# LatchingFaultActiveHigh.net
KiCad netlist of a schematic drawn in Altium Designer
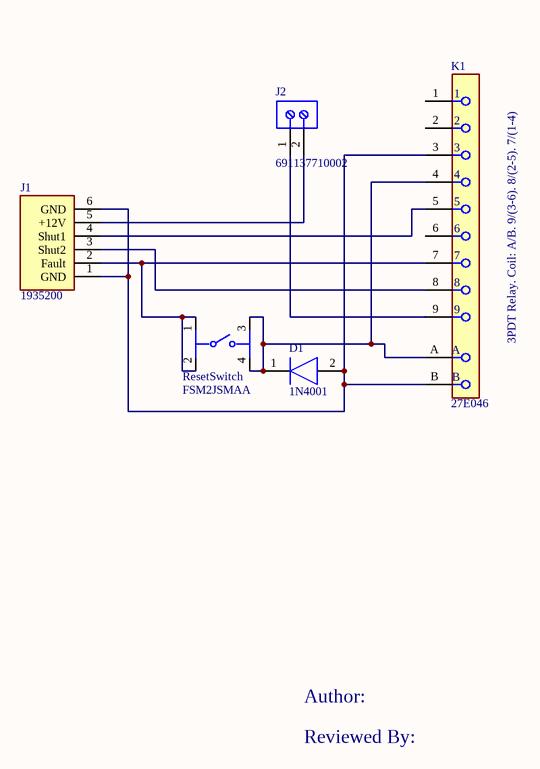
[diagram p0: LatchingFaultActiveHigh.SchDoc]

(export (version "E")
  (design (tool "Eeschema 10.0.6"))
  (components
    (comp (ref "D1")
      (value "1N4001")
      (footprint "SamacSys:DIOAD1410W86L470D235")
      (description "Diode")
      (libsource (lib "*") (part "1N4001"))
    )
    (comp (ref "J1")
      (value "1935200")
      (footprint "SamacSys:1935200")
      (description "Connector")
      (fields (field (name "MOUSER PART NUMBER") "651-1935200") (field (name "RS PART NUMBER") "8045509"))
      (libsource (lib "*") (part "1935200"))
    )
    (comp (ref "J2")
      (value "691137710002")
      (footprint "691137710002")
      (description "Series 1377 - 5.00 mm Horizontal Entry with Pressure Clamp WR-TBL, 2 pin")
      (fields (field (name "MANUFACTURER") "Wurth Elektronik") (field (name "PUBLISHER") "WurthElektronik"))
      (libsource (lib "Altium Content Vault") (part "WE-CN-1P-F-TB2"))
    )
    (comp (ref "K1")
      (value "27E046")
      (footprint "FP-27E046-MFG")
      (description "RELAY SOCKET 11 POS THROUGH HOLE")
      (fields
        (field (name "OCTOPART") "https://octopart.com/27e046-te+connectivity-39661310")
        (field (name "MANUFACTURER") "TE Connectivity")
      )
      (libsource (lib "Altium Content Vault") (part "d5e8f7d71913d095abaa3b4fe508f1c"))
    )
    (comp (ref "ResetSwitch")
      (value "FSM2JSMAA")
      (footprint "FP-FSM2JSMAA-MFG")
      (description "SWITCH TACTILE SPST-NO 0.05A 24V")
      (fields
        (field (name "MANUFACTURER") "TE Connectivity")
        (field (name "OCTOPART") "https://octopart.com/fsm2jsmaa-te+connectivity-41720620")
      )
      (libsource (lib "Altium Content Vault") (part "b8895f3f4cefb76e1819d2863dba89b"))
    )
  )
  (nets
    (net (code "1") (name "Net-(D1-A)") (class "Default")
      (node (ref "D1") (pin "2") (pinfunction "A_2") (pintype "passive"))
      (node (ref "J1") (pin "1") (pinfunction "GND_1") (pintype "passive"))
      (node (ref "J1") (pin "6") (pinfunction "GND_6") (pintype "passive"))
      (node (ref "K1") (pin "3") (pinfunction "3_3") (pintype "passive"))
      (node (ref "K1") (pin "B") (pinfunction "B_B") (pintype "passive"))
    )
    (net (code "2") (name "Net-(D1-K)") (class "Default")
      (node (ref "D1") (pin "1") (pinfunction "K_1") (pintype "passive"))
      (node (ref "K1") (pin "4") (pinfunction "4_4") (pintype "passive"))
      (node (ref "K1") (pin "A") (pinfunction "A_A") (pintype "passive"))
      (node (ref "ResetSwitch") (pin "3") (pinfunction "3_3") (pintype "passive"))
      (node (ref "ResetSwitch") (pin "4") (pinfunction "4_4") (pintype "passive"))
    )
    (net (code "3") (name "Net-(J1-+12V)") (class "Default")
      (node (ref "J1") (pin "5") (pinfunction "+12V_5") (pintype "passive"))
      (node (ref "J2") (pin "2") (pintype "passive"))
    )
    (net (code "4") (name "Net-(J1-Fault)") (class "Default")
      (node (ref "J1") (pin "2") (pinfunction "Fault_2") (pintype "passive"))
      (node (ref "K1") (pin "7") (pinfunction "7_7") (pintype "passive"))
      (node (ref "ResetSwitch") (pin "1") (pinfunction "1_1") (pintype "passive"))
      (node (ref "ResetSwitch") (pin "2") (pinfunction "2_2") (pintype "passive"))
    )
    (net (code "5") (name "Net-(J1-Shut1)") (class "Default")
      (node (ref "J1") (pin "4") (pinfunction "Shut1_4") (pintype "passive"))
      (node (ref "K1") (pin "5") (pinfunction "5_5") (pintype "passive"))
    )
    (net (code "6") (name "Net-(J1-Shut2)") (class "Default")
      (node (ref "J1") (pin "3") (pinfunction "Shut2_3") (pintype "passive"))
      (node (ref "K1") (pin "8") (pinfunction "8_8") (pintype "passive"))
    )
    (net (code "7") (name "Net-(J2-Pad1)") (class "Default")
      (node (ref "J2") (pin "1") (pinfunction "1_1") (pintype "passive"))
      (node (ref "K1") (pin "9") (pinfunction "9_9") (pintype "passive"))
    )
    (net (code "8") (name "unconnected-(K1-Pad1)") (class "Default")
      (node (ref "K1") (pin "1") (pinfunction "1_1") (pintype "passive"))
    )
    (net (code "9") (name "unconnected-(K1-Pad2)") (class "Default")
      (node (ref "K1") (pin "2") (pinfunction "2_2") (pintype "passive"))
    )
    (net (code "10") (name "unconnected-(K1-Pad6)") (class "Default")
      (node (ref "K1") (pin "6") (pinfunction "6_6") (pintype "passive"))
    )
  )
)
